# POWER.net
KiCad netlist of a schematic drawn in Altium Designer
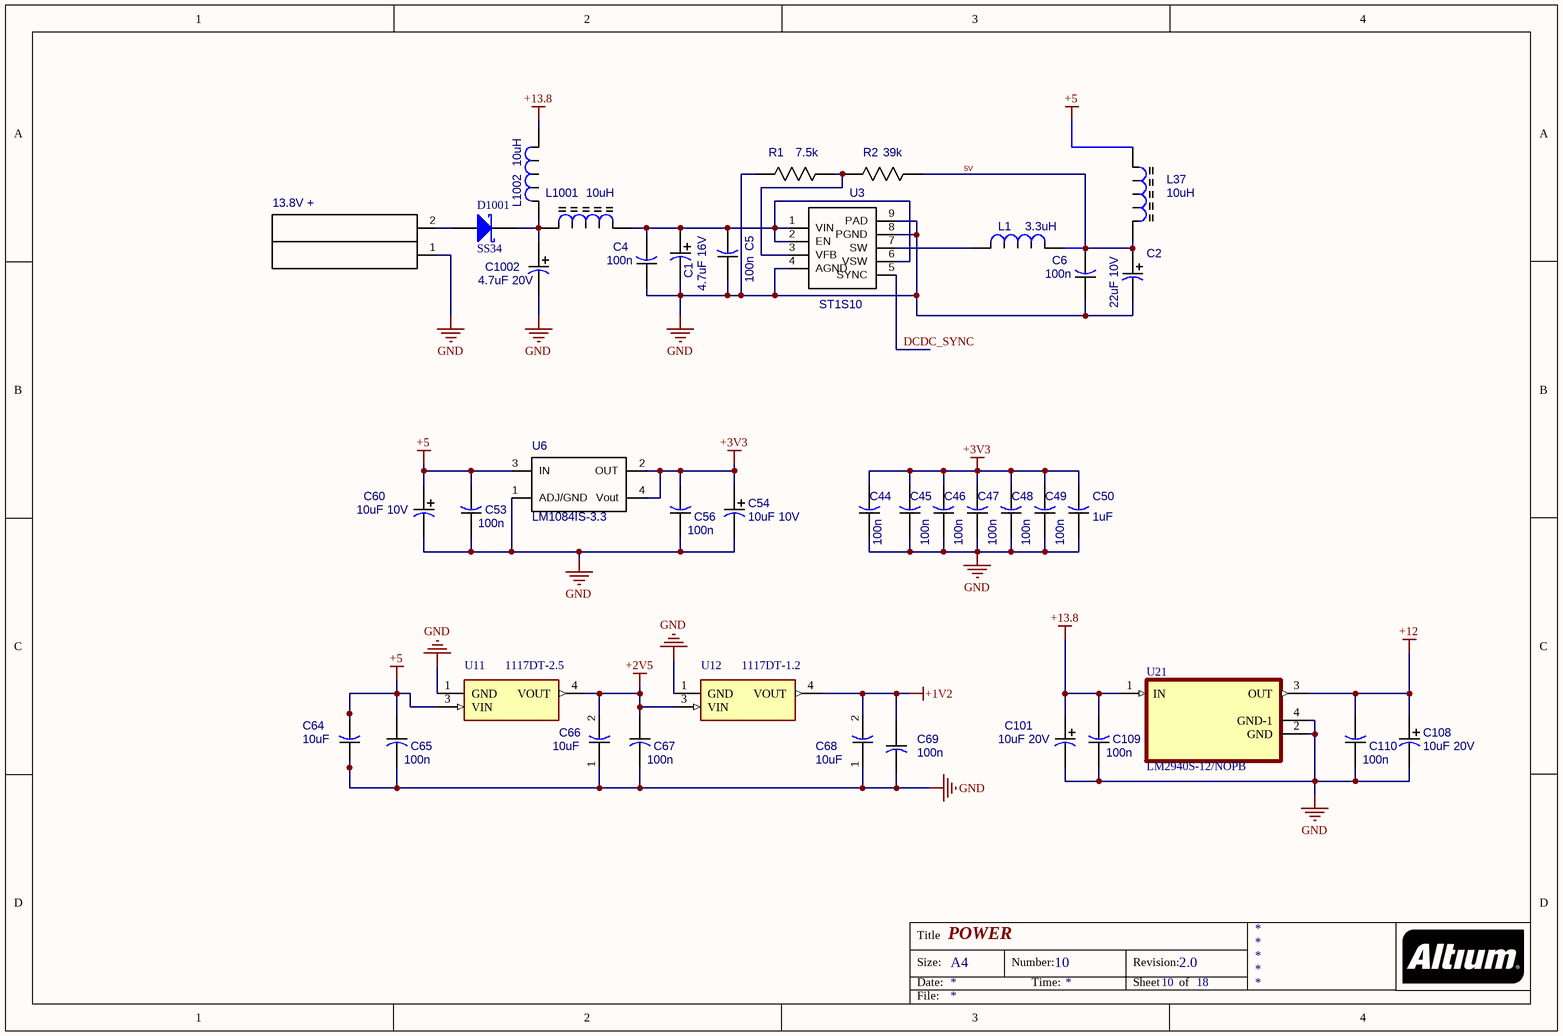
[diagram p0: POWER.SchDoc]

(export (version "E")
  (design (tool "Eeschema 10.0.6"))
  (components
    (comp (ref "13.8V +") (value "JX2") (footprint "JX2") (libsource (lib "*") (part "JX2")))
    (comp (ref "C1")
      (value "4.7uF 16V")
      (footprint "SMC")
      (description "CAPAE_6.6x6.6h5.4")
      (libsource (lib "*") (part "CAPAE_6.6x6.6h5.4"))
    )
    (comp (ref "C2")
      (value "22uF 10V")
      (footprint "CAPAE_4.3x4.3h5.4")
      (description "CAPAE_4.3x4.3h5.4")
      (libsource (lib "*") (part "CAPAE_4.3x4.3h5.4"))
    )
    (comp (ref "C4")
      (value "100n")
      (footprint "CAP_0805")
      (description "CAP_0805")
      (libsource (lib "*") (part "CAP_0805"))
    )
    (comp (ref "C5")
      (value "100n")
      (footprint "CAP_0805")
      (description "CAP_0805")
      (libsource (lib "*") (part "CAP_0805"))
    )
    (comp (ref "C6")
      (value "100n")
      (footprint "CAP_0805")
      (description "CAP_0805")
      (libsource (lib "*") (part "CAP_0805"))
    )
    (comp (ref "C44")
      (value "100n")
      (footprint "CAP_0805")
      (description "CAP_0805")
      (libsource (lib "*") (part "CAP_0805"))
    )
    (comp (ref "C45")
      (value "100n")
      (footprint "CAP_0805")
      (description "CAP_0805")
      (libsource (lib "*") (part "CAP_0805"))
    )
    (comp (ref "C46")
      (value "100n")
      (footprint "CAP_0805")
      (description "CAP_0805")
      (libsource (lib "*") (part "CAP_0805"))
    )
    (comp (ref "C47")
      (value "100n")
      (footprint "CAP_0805")
      (description "CAP_0805")
      (libsource (lib "*") (part "CAP_0805"))
    )
    (comp (ref "C48")
      (value "100n")
      (footprint "CAP_0805")
      (description "CAP_0805")
      (libsource (lib "*") (part "CAP_0805"))
    )
    (comp (ref "C49")
      (value "100n")
      (footprint "CAP_0805")
      (description "CAP_0805")
      (libsource (lib "*") (part "CAP_0805"))
    )
    (comp (ref "C50")
      (value "1uF")
      (footprint "CAP_0805")
      (description "CAP_0805")
      (fields (field (name "Comment") "10uF"))
      (libsource (lib "*") (part "CAP_0805"))
    )
    (comp (ref "C53")
      (value "100n")
      (footprint "CAP_0805")
      (description "CAP_0805")
      (libsource (lib "*") (part "CAP_0805"))
    )
    (comp (ref "C54")
      (value "10uF 10V")
      (footprint "CAPAE_4.3x4.3h5.4")
      (description "CAPAE_4.3x4.3h5.4")
      (libsource (lib "*") (part "CAPAE_4.3x4.3h5.4"))
    )
    (comp (ref "C56")
      (value "100n")
      (footprint "CAP_0805")
      (description "CAP_0805")
      (libsource (lib "*") (part "CAP_0805"))
    )
    (comp (ref "C60")
      (value "10uF 10V")
      (footprint "CAPAE_4.3x4.3h5.4")
      (description "CAPAE_4.3x4.3h5.4")
      (libsource (lib "*") (part "CAPAE_4.3x4.3h5.4"))
    )
    (comp (ref "C64")
      (value "10uF")
      (footprint "CAP_0805")
      (description "CAP_0805")
      (libsource (lib "") (part "CAP_0805_1"))
    )
    (comp (ref "C65")
      (value "100n")
      (footprint "CAP_0805")
      (description "CAP_0805")
      (libsource (lib "*") (part "CAP_0805"))
    )
    (comp (ref "C66")
      (value "10uF")
      (footprint "CAP_0805")
      (description "CAP_0805")
      (libsource (lib "MOTHERBOARD") (part "CAP_0805"))
    )
    (comp (ref "C67")
      (value "100n")
      (footprint "CAP_0805")
      (description "CAP_0805")
      (libsource (lib "*") (part "CAP_0805"))
    )
    (comp (ref "C68")
      (value "10uF")
      (footprint "CAP_0805")
      (description "CAP_0805")
      (libsource (lib "MOTHERBOARD") (part "CAP_0805"))
    )
    (comp (ref "C69")
      (value "100n")
      (footprint "CAP_0805")
      (description "CAP_0805")
      (libsource (lib "*") (part "CAP_0805"))
    )
    (comp (ref "C101")
      (value "10uF 20V")
      (footprint "CAPAE_4.3x4.3h5.4")
      (description "CAPAE_4.3x4.3h5.4")
      (libsource (lib "*") (part "CAPAE_4.3x4.3h5.4"))
    )
    (comp (ref "C108")
      (value "10uF 20V")
      (footprint "CAPAE_4.3x4.3h5.4")
      (description "CAPAE_4.3x4.3h5.4")
      (libsource (lib "*") (part "CAPAE_4.3x4.3h5.4"))
    )
    (comp (ref "C109")
      (value "100n")
      (footprint "CAP_0805")
      (description "CAP_0805")
      (libsource (lib "*") (part "CAP_0805"))
    )
    (comp (ref "C110")
      (value "100n")
      (footprint "CAP_0805")
      (description "CAP_0805")
      (libsource (lib "*") (part "CAP_0805"))
    )
    (comp (ref "C1002")
      (value "4.7uF 20V")
      (footprint "CAPAE_4.3x4.3h5.4")
      (description "CAPAE_4.3x4.3h5.4")
      (fields (field (name "Comment") "10uF 10V"))
      (libsource (lib "*") (part "CAPAE_4.3x4.3h5.4"))
    )
    (comp (ref "D1001")
      (value "SS34")
      (footprint "SMB")
      (description "Schottky Diode")
      (fields (field (name "PUBLISHER") "Altium Limited"))
      (libsource (lib "Miscellaneous Devices") (part "D Schottky"))
    )
    (comp (ref "L1")
      (value "3.3uH")
      (footprint "IND_1812")
      (description "IND_1812")
      (libsource (lib "*") (part "IND_1812"))
    )
    (comp (ref "L37")
      (value "10uH")
      (footprint "IND_7x7")
      (description "Inductor")
      (libsource (lib "MOTHERBOARD_1") (part "IND_FERRITE_CORE"))
    )
    (comp (ref "L1001")
      (value "10uH")
      (footprint "IND_7x7")
      (description "Inductor")
      (libsource (lib "MOTHERBOARD_1") (part "IND_FERRITE_CORE"))
    )
    (comp (ref "L1002")
      (value "10uH")
      (footprint "IND_1812")
      (description "IND_1812")
      (libsource (lib "*") (part "IND_1812"))
    )
    (comp (ref "R1")
      (value "7.5k")
      (footprint "RES_0805")
      (description "RES_0805")
      (libsource (lib "*") (part "RES_0805"))
    )
    (comp (ref "R2")
      (value "39k")
      (footprint "RES_0805")
      (description "RES_0805")
      (libsource (lib "*") (part "RES_0805"))
    )
    (comp (ref "U3") (value "ST1S10") (footprint "ST1S10") (libsource (lib "*") (part "ST1S10")))
    (comp (ref "U6")
      (value "LM1084IS-3.3")
      (footprint "LM1085-3.3")
      (libsource (lib "*") (part "LM1085-3.3"))
    )
    (comp (ref "U11")
      (value "1117DT-2.5")
      (footprint "SamacSys:TO228P991X238-3N")
      (description "LD1117DT-2.5 DPAK")
      (fields
        (field (name "MANUFACTURER_PART_NUMBER") "LM1117DT-ADJ")
        (field (name "MOUSER PART NUMBER") "926-LM1117DT-ADJ")
      )
      (libsource (lib "*") (part "LM1117DT-ADJ"))
    )
    (comp (ref "U12")
      (value "1117DT-1.2")
      (footprint "SamacSys:TO228P991X238-3N")
      (description "LD1117DT-1.2 DPAK")
      (fields
        (field (name "MANUFACTURER_PART_NUMBER") "LM1117DT-ADJ")
        (field (name "MOUSER PART NUMBER") "926-LM1117DT-ADJ")
      )
      (libsource (lib "*") (part "LM1117DT-ADJ"))
    )
    (comp (ref "U21")
      (value "LM2940S-12/NOPB")
      (footprint "TO254P1524X483-4N")
      (description "1-A, 26-V, high-PSRR, low-dropout voltage regulator")
      (fields (field (name "MF") "Texas Instruments"))
      (libsource (lib "LM2940S-12_NOPB") (part "LM2940S-12/NOPB"))
    )
  )
  (nets
    (net (code "1") (name "+1V2") (class "Default")
      (node (ref "C68") (pin "2") (pinfunction "2_2") (pintype "passive"))
      (node (ref "C69") (pin "1") (pinfunction "1_1") (pintype "passive"))
      (node (ref "U12") (pin "4") (pinfunction "VOUT_4") (pintype "output"))
    )
    (net (code "2") (name "+2V5") (class "Default")
      (node (ref "C66") (pin "2") (pinfunction "2_2") (pintype "passive"))
      (node (ref "C67") (pin "1") (pinfunction "1_1") (pintype "passive"))
      (node (ref "U11") (pin "4") (pinfunction "VOUT_4") (pintype "output"))
      (node (ref "U12") (pin "3") (pinfunction "VIN_3") (pintype "input"))
    )
    (net (code "3") (name "+3V3") (class "Default")
      (node (ref "C44") (pin "2") (pinfunction "2_2") (pintype "passive"))
      (node (ref "C45") (pin "2") (pinfunction "2_2") (pintype "passive"))
      (node (ref "C46") (pin "2") (pinfunction "2_2") (pintype "passive"))
      (node (ref "C47") (pin "2") (pinfunction "2_2") (pintype "passive"))
      (node (ref "C48") (pin "2") (pinfunction "2_2") (pintype "passive"))
      (node (ref "C49") (pin "2") (pinfunction "2_2") (pintype "passive"))
      (node (ref "C50") (pin "2") (pinfunction "2_2") (pintype "passive"))
      (node (ref "C54") (pin "1") (pinfunction "PLUS_1") (pintype "passive"))
      (node (ref "C56") (pin "2") (pinfunction "2_2") (pintype "passive"))
      (node (ref "U6") (pin "2") (pinfunction "OUT_2") (pintype "passive"))
      (node (ref "U6") (pin "4") (pinfunction "Vout_4") (pintype "passive"))
    )
    (net (code "4") (name "+5") (class "Default")
      (node (ref "C53") (pin "2") (pinfunction "2_2") (pintype "passive"))
      (node (ref "C60") (pin "1") (pinfunction "PLUS_1") (pintype "passive"))
      (node (ref "C64") (pin "2") (pinfunction "2_2") (pintype "passive"))
      (node (ref "C65") (pin "1") (pinfunction "1_1") (pintype "passive"))
      (node (ref "L37") (pin "1") (pinfunction "A_1") (pintype "passive"))
      (node (ref "U11") (pin "3") (pinfunction "VIN_3") (pintype "input"))
      (node (ref "U6") (pin "3") (pinfunction "IN_3") (pintype "passive"))
    )
    (net (code "5") (name "+12") (class "Default")
      (node (ref "C108") (pin "1") (pinfunction "PLUS_1") (pintype "passive"))
      (node (ref "C110") (pin "2") (pinfunction "2_2") (pintype "passive"))
      (node (ref "U21") (pin "3") (pinfunction "OUT_3") (pintype "output"))
    )
    (net (code "6") (name "+13.8") (class "Default")
      (node (ref "C101") (pin "1") (pinfunction "PLUS_1") (pintype "passive"))
      (node (ref "C109") (pin "2") (pinfunction "2_2") (pintype "passive"))
      (node (ref "L1002") (pin "2") (pinfunction "2_2") (pintype "passive"))
      (node (ref "U21") (pin "1") (pinfunction "IN_1") (pintype "input"))
    )
    (net (code "7") (name "/5V") (class "Default")
      (node (ref "C2") (pin "1") (pinfunction "PLUS_1") (pintype "passive"))
      (node (ref "C6") (pin "2") (pinfunction "2_2") (pintype "passive"))
      (node (ref "L1") (pin "2") (pinfunction "2_2") (pintype "passive"))
      (node (ref "L37") (pin "2") (pinfunction "B_2") (pintype "passive"))
      (node (ref "R2") (pin "2") (pinfunction "2_2") (pintype "passive"))
    )
    (net (code "8") (name "/DCDC_SYNC") (class "Default")
      (node (ref "U3") (pin "5") (pinfunction "SYNC_5") (pintype "passive"))
    )
    (net (code "9") (name "GND") (class "Default")
      (node (ref "13.8V +") (pin "1") (pinfunction "2_1") (pintype "passive"))
      (node (ref "C1") (pin "2") (pinfunction "MINUS_2") (pintype "passive"))
      (node (ref "C1002") (pin "2") (pinfunction "MINUS_2") (pintype "passive"))
      (node (ref "C101") (pin "2") (pinfunction "MINUS_2") (pintype "passive"))
      (node (ref "C108") (pin "2") (pinfunction "MINUS_2") (pintype "passive"))
      (node (ref "C109") (pin "1") (pinfunction "1_1") (pintype "passive"))
      (node (ref "C110") (pin "1") (pinfunction "1_1") (pintype "passive"))
      (node (ref "C2") (pin "2") (pinfunction "MINUS_2") (pintype "passive"))
      (node (ref "C4") (pin "1") (pinfunction "1_1") (pintype "passive"))
      (node (ref "C44") (pin "1") (pinfunction "1_1") (pintype "passive"))
      (node (ref "C45") (pin "1") (pinfunction "1_1") (pintype "passive"))
      (node (ref "C46") (pin "1") (pinfunction "1_1") (pintype "passive"))
      (node (ref "C47") (pin "1") (pinfunction "1_1") (pintype "passive"))
      (node (ref "C48") (pin "1") (pinfunction "1_1") (pintype "passive"))
      (node (ref "C49") (pin "1") (pinfunction "1_1") (pintype "passive"))
      (node (ref "C5") (pin "1") (pinfunction "1_1") (pintype "passive"))
      (node (ref "C50") (pin "1") (pinfunction "1_1") (pintype "passive"))
      (node (ref "C53") (pin "1") (pinfunction "1_1") (pintype "passive"))
      (node (ref "C54") (pin "2") (pinfunction "MINUS_2") (pintype "passive"))
      (node (ref "C56") (pin "1") (pinfunction "1_1") (pintype "passive"))
      (node (ref "C6") (pin "1") (pinfunction "1_1") (pintype "passive"))
      (node (ref "C60") (pin "2") (pinfunction "MINUS_2") (pintype "passive"))
      (node (ref "C64") (pin "1") (pinfunction "1_1") (pintype "passive"))
      (node (ref "C65") (pin "2") (pinfunction "2_2") (pintype "passive"))
      (node (ref "C66") (pin "1") (pinfunction "1_1") (pintype "passive"))
      (node (ref "C67") (pin "2") (pinfunction "2_2") (pintype "passive"))
      (node (ref "C68") (pin "1") (pinfunction "1_1") (pintype "passive"))
      (node (ref "C69") (pin "2") (pinfunction "2_2") (pintype "passive"))
      (node (ref "R1") (pin "1") (pinfunction "1_1") (pintype "passive"))
      (node (ref "U11") (pin "1") (pinfunction "GND_1") (pintype "passive"))
      (node (ref "U12") (pin "1") (pinfunction "GND_1") (pintype "passive"))
      (node (ref "U21") (pin "2") (pinfunction "GND_2") (pintype "power_in"))
      (node (ref "U21") (pin "4") (pinfunction "GND-1_4") (pintype "power_in"))
      (node (ref "U3") (pin "4") (pinfunction "AGND_4") (pintype "passive"))
      (node (ref "U3") (pin "8") (pinfunction "PGND_8") (pintype "passive"))
      (node (ref "U3") (pin "9") (pinfunction "PAD_9") (pintype "passive"))
      (node (ref "U6") (pin "1") (pinfunction "ADJ/GND_1") (pintype "passive"))
    )
    (net (code "10") (name "Net-(13.8V +-1)") (class "Default")
      (node (ref "13.8V +") (pin "2") (pinfunction "1_2") (pintype "passive"))
      (node (ref "D1001") (pin "1") (pinfunction "A_1") (pintype "passive"))
    )
    (net (code "11") (name "Net-(C1-PLUS)") (class "Default")
      (node (ref "C1") (pin "1") (pinfunction "PLUS_1") (pintype "passive"))
      (node (ref "C4") (pin "2") (pinfunction "2_2") (pintype "passive"))
      (node (ref "C5") (pin "2") (pinfunction "2_2") (pintype "passive"))
      (node (ref "L1001") (pin "2") (pinfunction "B_2") (pintype "passive"))
      (node (ref "U3") (pin "1") (pinfunction "VIN_1") (pintype "passive"))
      (node (ref "U3") (pin "2") (pinfunction "EN_2") (pintype "passive"))
      (node (ref "U3") (pin "6") (pinfunction "VSW_6") (pintype "passive"))
    )
    (net (code "12") (name "Net-(C1002-PLUS)") (class "Default")
      (node (ref "C1002") (pin "1") (pinfunction "PLUS_1") (pintype "passive"))
      (node (ref "D1001") (pin "2") (pinfunction "K_2") (pintype "passive"))
      (node (ref "L1001") (pin "1") (pinfunction "A_1") (pintype "passive"))
      (node (ref "L1002") (pin "1") (pinfunction "1_1") (pintype "passive"))
    )
    (net (code "13") (name "Net-(U3-SW)") (class "Default")
      (node (ref "L1") (pin "1") (pinfunction "1_1") (pintype "passive"))
      (node (ref "U3") (pin "7") (pinfunction "SW_7") (pintype "passive"))
    )
    (net (code "14") (name "Net-(U3-VFB)") (class "Default")
      (node (ref "R1") (pin "2") (pinfunction "2_2") (pintype "passive"))
      (node (ref "R2") (pin "1") (pinfunction "1_1") (pintype "passive"))
      (node (ref "U3") (pin "3") (pinfunction "VFB_3") (pintype "passive"))
    )
  )
)
